# Regulator.net
KiCad netlist of a schematic drawn in Altium Designer
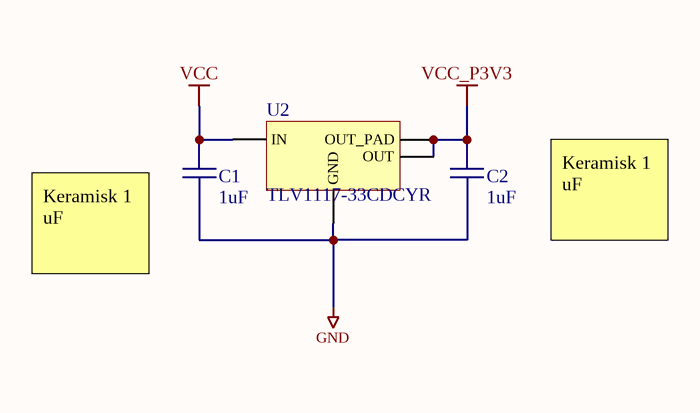
[diagram p0: Regulator.SchDoc]

(export (version "E")
  (design (tool "Eeschema 10.0.6"))
  (components
    (comp (ref "C1")
      (value "1uF")
      (footprint "CAPC0805(2012)100_N")
      (description "X7R 50V 10%")
      (libsource (lib "OVLib") (part "CAP"))
    )
    (comp (ref "C2")
      (value "1uF")
      (footprint "CAPC0805(2012)100_N")
      (description "X7R 50V 10%")
      (libsource (lib "OVLib") (part "CAP"))
    )
    (comp (ref "U2")
      (value "TLV1117-33CDCYR")
      (footprint "SOT230P700X180-4N")
      (description "3,3V Low dropout regulator")
      (libsource (lib "OVLib") (part "LDO_REGULATOR"))
    )
  )
  (nets
    (net (code "1") (name "GND") (class "Default")
      (node (ref "C1") (pin "1") (pinfunction "1_1") (pintype "passive"))
      (node (ref "C2") (pin "1") (pinfunction "1_1") (pintype "passive"))
      (node (ref "U2") (pin "1") (pinfunction "GND_1") (pintype "power_in"))
    )
    (net (code "2") (name "VCC") (class "Default")
      (node (ref "C1") (pin "2") (pinfunction "2_2") (pintype "passive"))
      (node (ref "U2") (pin "3") (pinfunction "IN_3") (pintype "power_in"))
    )
    (net (code "3") (name "VCC_P3V3") (class "Default")
      (node (ref "C2") (pin "2") (pinfunction "2_2") (pintype "passive"))
      (node (ref "U2") (pin "2") (pinfunction "OUT_PAD_2") (pintype "power_in"))
      (node (ref "U2") (pin "4") (pinfunction "OUT_4") (pintype "power_in"))
    )
  )
)
